# Sheet_LoraE32_Receive_V1_0.net
KiCad netlist of a schematic drawn in Altium Designer
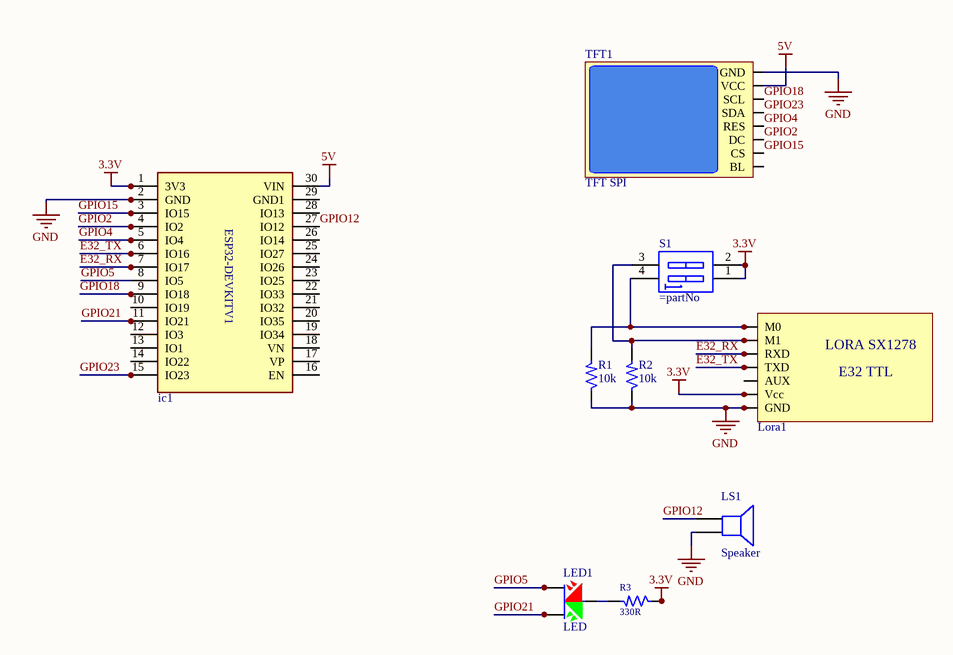
[diagram p0: Sheet_LoraE32_Receive_V1.0.SchDoc]

(export (version "E")
  (design (tool "Eeschema 10.0.6"))
  (components
    (comp (ref "ic1")
      (value "ESP32 DevKit 30Pin")
      (footprint "ESP32 DevKit V1 30Pin CAo")
      (libsource (lib "TCT Library") (part "ESP32 DevKit 30Pin"))
    )
    (comp (ref "LED1")
      (value "LED")
      (footprint "LED-52")
      (description "Anot Comment Green and Red")
      (libsource (lib "my Library") (part "LED 2A"))
    )
    (comp (ref "Lora1")
      (value "LORA E32 TTL")
      (footprint "LORA E32 TTL CAO")
      (libsource (lib "TCT Library") (part "LORA E32 TTL"))
    )
    (comp (ref "LS1")
      (value "Speaker")
      (footprint "SPEAKER")
      (description "Loudspeaker")
      (fields (field (name "PUBLISHER") "Altium Limited"))
      (libsource (lib "My Library") (part "Speaker"))
    )
    (comp (ref "R1")
      (value "10k")
      (footprint "R1/4W")
      (description "Res")
      (libsource (lib "my Library") (part "Res DIP"))
    )
    (comp (ref "R2")
      (value "10k")
      (footprint "R1/4W")
      (description "Res")
      (libsource (lib "my Library") (part "Res DIP"))
    )
    (comp (ref "R3")
      (value "330R")
      (footprint "RES-1206")
      (description "Res")
      (libsource (lib "my Library") (part "Res SMD"))
    )
    (comp (ref "S1")
      (value "~")
      (footprint "SW-DIP2")
      (description "WS-DITV 2.54 mm small compact THT flat actuator with top tape")
      (fields
        (field (name "MANUFACTURER") "Wurth Elektronik")
        (field (name "PART NO.") "418127160902")
        (field (name "CREATED BY") "Baojun Chen")
      )
      (libsource (lib "TechMT.VN_Lib_Project v2") (part "SWDIP2"))
    )
    (comp (ref "TFT1")
      (value "TFT SPI")
      (footprint "TFT 1.8 SPI")
      (libsource (lib "TCT Library") (part "TFT SPI"))
    )
  )
  (nets
    (net (code "1") (name "/E32_RX") (class "Default")
      (node (ref "Lora1") (pin "5") (pinfunction "RXD_5") (pintype "passive"))
      (node (ref "ic1") (pin "7") (pinfunction "IO17_7") (pintype "passive"))
    )
    (net (code "2") (name "/E32_TX") (class "Default")
      (node (ref "Lora1") (pin "4") (pinfunction "TXD_4") (pintype "passive"))
      (node (ref "ic1") (pin "6") (pinfunction "IO16_6") (pintype "passive"))
    )
    (net (code "3") (name "/GPIO2") (class "Default")
      (node (ref "TFT1") (pin "DC") (pinfunction "DC_DC") (pintype "passive"))
      (node (ref "ic1") (pin "4") (pinfunction "IO2_4") (pintype "passive"))
    )
    (net (code "4") (name "/GPIO4") (class "Default")
      (node (ref "TFT1") (pin "RES") (pinfunction "RES_RES") (pintype "passive"))
      (node (ref "ic1") (pin "5") (pinfunction "IO4_5") (pintype "passive"))
    )
    (net (code "5") (name "/GPIO5") (class "Default")
      (node (ref "LED1") (pin "1") (pinfunction "1_1") (pintype "passive"))
      (node (ref "ic1") (pin "8") (pinfunction "IO5_8") (pintype "passive"))
    )
    (net (code "6") (name "/GPIO12") (class "Default")
      (node (ref "LS1") (pin "1") (pinfunction "1_1") (pintype "passive"))
      (node (ref "ic1") (pin "27") (pinfunction "IO12_27") (pintype "passive"))
    )
    (net (code "7") (name "/GPIO15") (class "Default")
      (node (ref "TFT1") (pin "CS") (pinfunction "CS_CS") (pintype "passive"))
      (node (ref "ic1") (pin "3") (pinfunction "IO15_3") (pintype "passive"))
    )
    (net (code "8") (name "/GPIO18") (class "Default")
      (node (ref "TFT1") (pin "SCL") (pinfunction "SCL_SCL") (pintype "passive"))
      (node (ref "ic1") (pin "9") (pinfunction "IO18_9") (pintype "passive"))
    )
    (net (code "9") (name "/GPIO21") (class "Default")
      (node (ref "LED1") (pin "3") (pinfunction "3_3") (pintype "passive"))
      (node (ref "ic1") (pin "11") (pinfunction "IO21_11") (pintype "passive"))
    )
    (net (code "10") (name "/GPIO23") (class "Default")
      (node (ref "TFT1") (pin "SDA") (pinfunction "SDA_SDA") (pintype "passive"))
      (node (ref "ic1") (pin "15") (pinfunction "IO23_15") (pintype "passive"))
    )
    (net (code "11") (name "3.3V") (class "Default")
      (node (ref "Lora1") (pin "2") (pinfunction "Vcc_2") (pintype "passive"))
      (node (ref "R3") (pin "1") (pinfunction "1_1") (pintype "passive"))
      (node (ref "S1") (pin "1") (pinfunction "1_1") (pintype "passive"))
      (node (ref "S1") (pin "2") (pinfunction "2_2") (pintype "passive"))
      (node (ref "ic1") (pin "1") (pinfunction "3V3_1") (pintype "passive"))
    )
    (net (code "12") (name "5V") (class "Default")
      (node (ref "TFT1") (pin "VCC") (pinfunction "VCC_VCC") (pintype "passive"))
      (node (ref "ic1") (pin "30") (pinfunction "VIN_30") (pintype "passive"))
    )
    (net (code "13") (name "GND") (class "Default")
      (node (ref "LS1") (pin "2") (pinfunction "2_2") (pintype "passive"))
      (node (ref "Lora1") (pin "1") (pinfunction "GND_1") (pintype "passive"))
      (node (ref "R1") (pin "1") (pinfunction "1_1") (pintype "passive"))
      (node (ref "R2") (pin "1") (pinfunction "1_1") (pintype "passive"))
      (node (ref "TFT1") (pin "GND") (pinfunction "GND_GND") (pintype "passive"))
      (node (ref "ic1") (pin "2") (pinfunction "GND_2") (pintype "passive"))
    )
    (net (code "14") (name "Net-(LED1-Pad2)") (class "Default")
      (node (ref "LED1") (pin "2") (pinfunction "2_2") (pintype "passive"))
      (node (ref "R3") (pin "2") (pinfunction "2_2") (pintype "passive"))
    )
    (net (code "15") (name "Net-(Lora1-M0)") (class "Default")
      (node (ref "Lora1") (pin "7") (pinfunction "M0_7") (pintype "passive"))
      (node (ref "R1") (pin "2") (pinfunction "2_2") (pintype "passive"))
      (node (ref "S1") (pin "4") (pinfunction "4_4") (pintype "passive"))
    )
    (net (code "16") (name "Net-(Lora1-M1)") (class "Default")
      (node (ref "Lora1") (pin "6") (pinfunction "M1_6") (pintype "passive"))
      (node (ref "R2") (pin "2") (pinfunction "2_2") (pintype "passive"))
      (node (ref "S1") (pin "3") (pinfunction "3_3") (pintype "passive"))
    )
    (net (code "17") (name "unconnected-(Lora1-AUX-Pad3)") (class "Default")
      (node (ref "Lora1") (pin "3") (pinfunction "AUX_3") (pintype "passive"))
    )
    (net (code "18") (name "unconnected-(TFT1-PadBL)") (class "Default")
      (node (ref "TFT1") (pin "BL") (pinfunction "BL_BL") (pintype "passive"))
    )
    (net (code "19") (name "unconnected-(ic1-EN-Pad16)") (class "Default")
      (node (ref "ic1") (pin "16") (pinfunction "EN_16") (pintype "passive"))
    )
    (net (code "20") (name "unconnected-(ic1-GND1-Pad29)") (class "Default")
      (node (ref "ic1") (pin "29") (pinfunction "GND1_29") (pintype "passive"))
    )
    (net (code "21") (name "unconnected-(ic1-IO1-Pad13)") (class "Default")
      (node (ref "ic1") (pin "13") (pinfunction "IO1_13") (pintype "passive"))
    )
    (net (code "22") (name "unconnected-(ic1-IO3-Pad12)") (class "Default")
      (node (ref "ic1") (pin "12") (pinfunction "IO3_12") (pintype "passive"))
    )
    (net (code "23") (name "unconnected-(ic1-IO13-Pad28)") (class "Default")
      (node (ref "ic1") (pin "28") (pinfunction "IO13_28") (pintype "passive"))
    )
    (net (code "24") (name "unconnected-(ic1-IO14-Pad26)") (class "Default")
      (node (ref "ic1") (pin "26") (pinfunction "IO14_26") (pintype "passive"))
    )
    (net (code "25") (name "unconnected-(ic1-IO19-Pad10)") (class "Default")
      (node (ref "ic1") (pin "10") (pinfunction "IO19_10") (pintype "passive"))
    )
    (net (code "26") (name "unconnected-(ic1-IO22-Pad14)") (class "Default")
      (node (ref "ic1") (pin "14") (pinfunction "IO22_14") (pintype "passive"))
    )
    (net (code "27") (name "unconnected-(ic1-IO25-Pad23)") (class "Default")
      (node (ref "ic1") (pin "23") (pinfunction "IO25_23") (pintype "passive"))
    )
    (net (code "28") (name "unconnected-(ic1-IO26-Pad24)") (class "Default")
      (node (ref "ic1") (pin "24") (pinfunction "IO26_24") (pintype "passive"))
    )
    (net (code "29") (name "unconnected-(ic1-IO27-Pad25)") (class "Default")
      (node (ref "ic1") (pin "25") (pinfunction "IO27_25") (pintype "passive"))
    )
    (net (code "30") (name "unconnected-(ic1-IO32-Pad21)") (class "Default")
      (node (ref "ic1") (pin "21") (pinfunction "IO32_21") (pintype "passive"))
    )
    (net (code "31") (name "unconnected-(ic1-IO33-Pad22)") (class "Default")
      (node (ref "ic1") (pin "22") (pinfunction "IO33_22") (pintype "passive"))
    )
    (net (code "32") (name "unconnected-(ic1-IO34-Pad19)") (class "Default")
      (node (ref "ic1") (pin "19") (pinfunction "IO34_19") (pintype "passive"))
    )
    (net (code "33") (name "unconnected-(ic1-IO35-Pad20)") (class "Default")
      (node (ref "ic1") (pin "20") (pinfunction "IO35_20") (pintype "passive"))
    )
    (net (code "34") (name "unconnected-(ic1-VN-Pad18)") (class "Default")
      (node (ref "ic1") (pin "18") (pinfunction "VN_18") (pintype "passive"))
    )
    (net (code "35") (name "unconnected-(ic1-VP-Pad17)") (class "Default")
      (node (ref "ic1") (pin "17") (pinfunction "VP_17") (pintype "passive"))
    )
  )
)
